# servo2.net
KiCad netlist of a schematic drawn in EAGLE
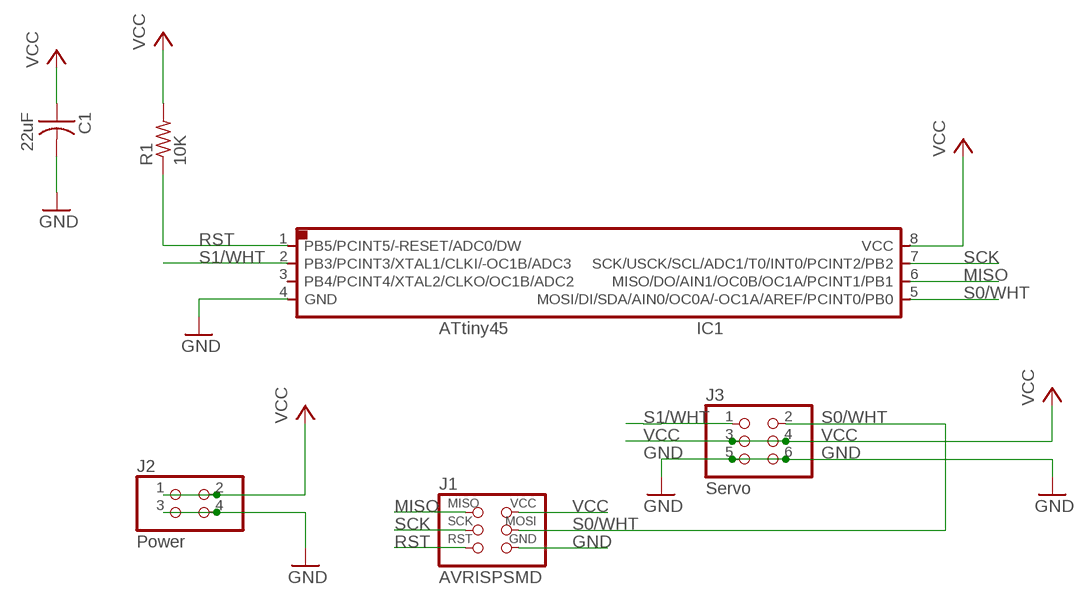
[diagram p0: schematic, sheet 1]

(export (version "E")
  (design (tool "Eeschema 10.0.6"))
  (components
    (comp (ref "C1")
      (value "22uF")
      (footprint "eagle-import:C1206FAB")
      (libsource (lib "eagle-import") (part "CAP-US1206FAB"))
    )
    (comp (ref "IC1")
      (value "ATTINY45SI")
      (footprint "eagle-import:SOIC8")
      (libsource (lib "eagle-import") (part "ATTINY45SI"))
    )
    (comp (ref "J1")
      (value "AVRISPSMD")
      (footprint "eagle-import:2X03SMD")
      (libsource (lib "eagle-import") (part "AVRISPSMD"))
    )
    (comp (ref "J2")
      (value "Power")
      (footprint "eagle-import:2X02SMD")
      (libsource (lib "eagle-import") (part "PINHD-2X2-SMD"))
    )
    (comp (ref "J3")
      (value "Servo")
      (footprint "eagle-import:2X03SMD")
      (libsource (lib "eagle-import") (part "PINHD-2X3-SMD"))
    )
    (comp (ref "R1")
      (value "10K")
      (footprint "eagle-import:R1206FAB")
      (libsource (lib "eagle-import") (part "RES-US1206FAB"))
    )
  )
  (nets
    (net (code "1") (name "/MISO") (class "Default")
      (node (ref "IC1") (pin "6") (pinfunction "MISO/DO/AIN1/OC0B/OC1A/PCINT1/PB1_6") (pintype "bidirectional"))
      (node (ref "J1") (pin "1") (pinfunction "MISO_1") (pintype "passive"))
    )
    (net (code "2") (name "/RST") (class "Default")
      (node (ref "IC1") (pin "1") (pinfunction "PB5/PCINT5/-RESET/ADC0/DW_1") (pintype "bidirectional"))
      (node (ref "J1") (pin "5") (pinfunction "RST_5") (pintype "passive"))
      (node (ref "R1") (pin "1") (pinfunction "1_1") (pintype "passive"))
    )
    (net (code "3") (name "/S0{slash}WHT") (class "Default")
      (node (ref "IC1") (pin "5") (pinfunction "MOSI/DI/SDA/AIN0/OC0A/-OC1A/AREF/PCINT0/PB0_5") (pintype "bidirectional"))
      (node (ref "J1") (pin "4") (pinfunction "MOSI_4") (pintype "passive"))
      (node (ref "J3") (pin "2") (pinfunction "2_2") (pintype "passive"))
    )
    (net (code "4") (name "/S1{slash}WHT") (class "Default")
      (node (ref "IC1") (pin "2") (pinfunction "PB3/PCINT3/XTAL1/CLKI/-OC1B/ADC3_2") (pintype "bidirectional"))
      (node (ref "J3") (pin "1") (pinfunction "1_1") (pintype "passive"))
    )
    (net (code "5") (name "/SCK") (class "Default")
      (node (ref "IC1") (pin "7") (pinfunction "SCK/USCK/SCL/ADC1/T0/INT0/PCINT2/PB2_7") (pintype "bidirectional"))
      (node (ref "J1") (pin "3") (pinfunction "SCK_3") (pintype "passive"))
    )
    (net (code "6") (name "GND") (class "Default")
      (node (ref "C1") (pin "2") (pinfunction "2_2") (pintype "passive"))
      (node (ref "IC1") (pin "4") (pinfunction "GND_4") (pintype "bidirectional"))
      (node (ref "J1") (pin "6") (pinfunction "GND_6") (pintype "passive"))
      (node (ref "J2") (pin "3") (pinfunction "3_3") (pintype "passive"))
      (node (ref "J2") (pin "4") (pinfunction "4_4") (pintype "passive"))
      (node (ref "J3") (pin "5") (pinfunction "5_5") (pintype "passive"))
      (node (ref "J3") (pin "6") (pinfunction "6_6") (pintype "passive"))
    )
    (net (code "7") (name "VCC") (class "Default")
      (node (ref "C1") (pin "1") (pinfunction "1_1") (pintype "passive"))
      (node (ref "IC1") (pin "8") (pinfunction "VCC_8") (pintype "bidirectional"))
      (node (ref "J1") (pin "2") (pinfunction "VCC_2") (pintype "passive"))
      (node (ref "J2") (pin "1") (pinfunction "1_1") (pintype "passive"))
      (node (ref "J2") (pin "2") (pinfunction "2_2") (pintype "passive"))
      (node (ref "J3") (pin "3") (pinfunction "3_3") (pintype "passive"))
      (node (ref "J3") (pin "4") (pinfunction "4_4") (pintype "passive"))
      (node (ref "R1") (pin "2") (pinfunction "2_2") (pintype "passive"))
    )
    (net (code "8") (name "unconnected-(IC1-PB4{slash}PCINT4{slash}XTAL2{slash}CLKO{slash}OC1B{slash}ADC2-Pad3)") (class "Default")
      (node (ref "IC1") (pin "3") (pinfunction "PB4/PCINT4/XTAL2/CLKO/OC1B/ADC2_3") (pintype "bidirectional"))
    )
  )
)
